# S6_Solenoid_Valve_Interlock.net
KiCad netlist of a schematic drawn in Altium Designer
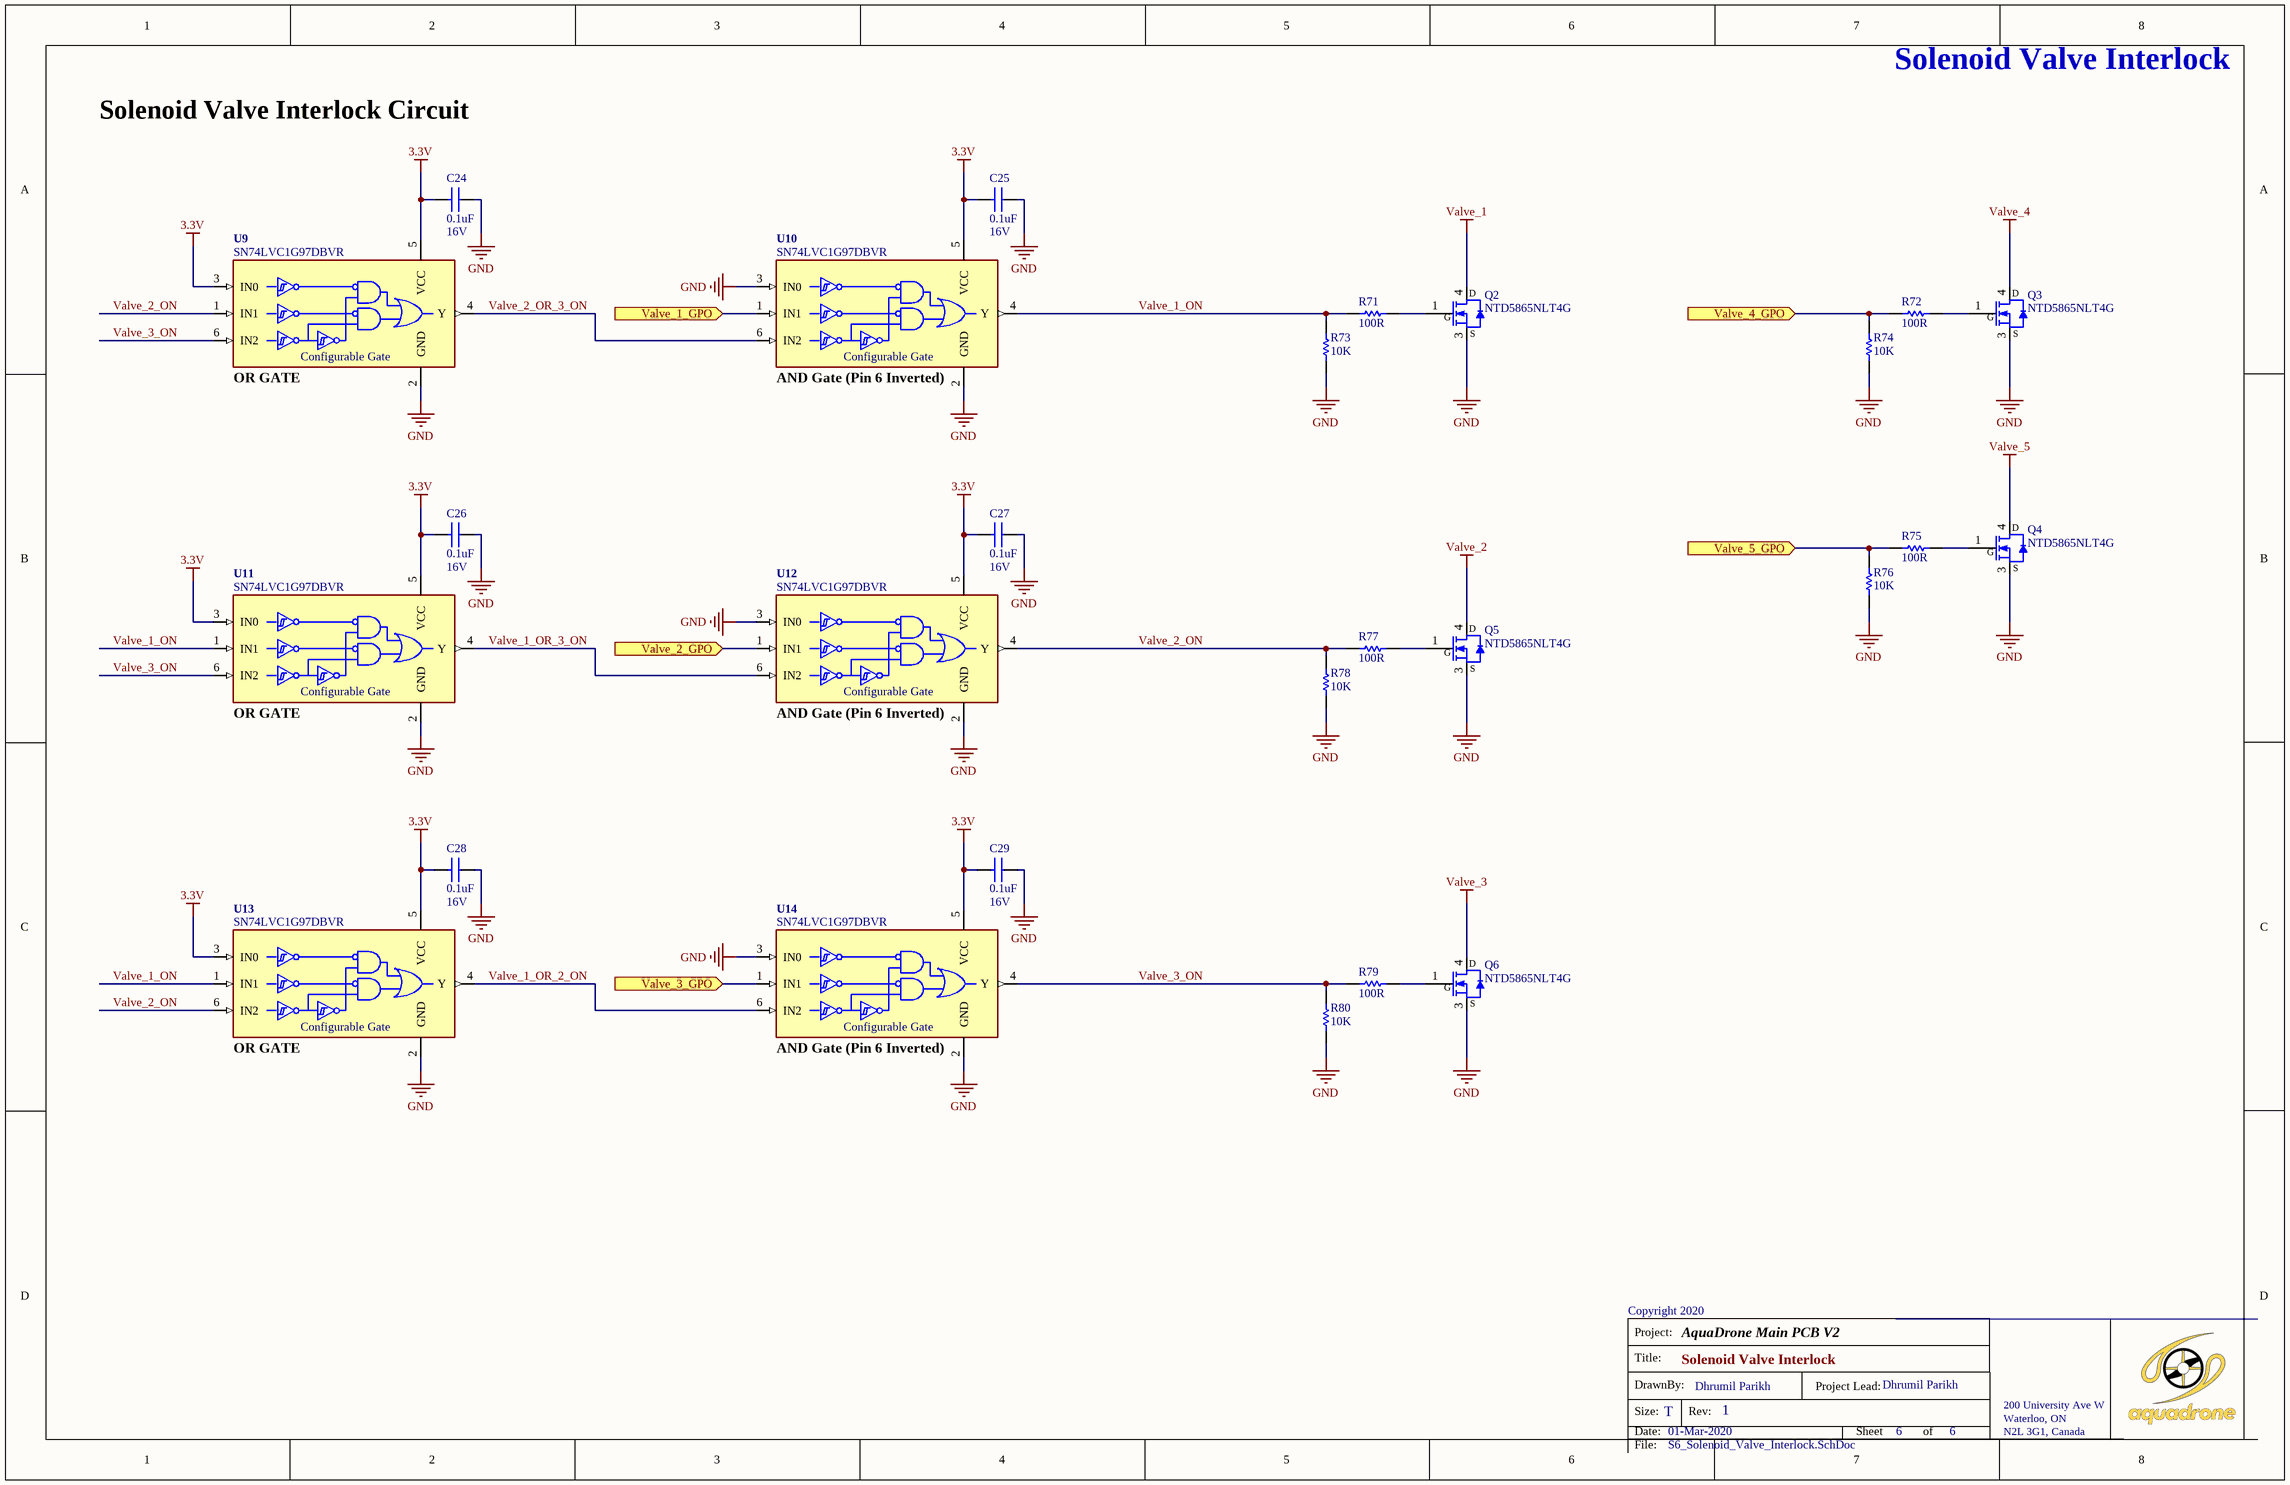
[diagram p0: S6_Solenoid_Valve_Interlock.SchDoc]

(export (version "E")
  (design (tool "Eeschema 10.0.6"))
  (components
    (comp (ref "C24")
      (value "0.1uF")
      (footprint "RWMN:CAPC1608X09N")
      (description "CAP CER 0.1UF 16V X7R 0603")
      (fields
        (field (name "MFG") "KEMET")
        (field (name "MFG_PART_NO") "C0603C104M4RACTU")
        (field (name "VOLTAGE") "16V")
      )
      (libsource (lib "AquaDrone") (part "CAP CER 0.1UF 16V X7R 0603"))
    )
    (comp (ref "C25")
      (value "0.1uF")
      (footprint "RWMN:CAPC1608X09N")
      (description "CAP CER 0.1UF 16V X7R 0603")
      (fields
        (field (name "MFG") "KEMET")
        (field (name "MFG_PART_NO") "C0603C104M4RACTU")
        (field (name "VOLTAGE") "16V")
      )
      (libsource (lib "AquaDrone") (part "CAP CER 0.1UF 16V X7R 0603"))
    )
    (comp (ref "C26")
      (value "0.1uF")
      (footprint "RWMN:CAPC1608X09N")
      (description "CAP CER 0.1UF 16V X7R 0603")
      (fields
        (field (name "MFG") "KEMET")
        (field (name "MFG_PART_NO") "C0603C104M4RACTU")
        (field (name "VOLTAGE") "16V")
      )
      (libsource (lib "AquaDrone") (part "CAP CER 0.1UF 16V X7R 0603"))
    )
    (comp (ref "C27")
      (value "0.1uF")
      (footprint "RWMN:CAPC1608X09N")
      (description "CAP CER 0.1UF 16V X7R 0603")
      (fields
        (field (name "MFG") "KEMET")
        (field (name "MFG_PART_NO") "C0603C104M4RACTU")
        (field (name "VOLTAGE") "16V")
      )
      (libsource (lib "AquaDrone") (part "CAP CER 0.1UF 16V X7R 0603"))
    )
    (comp (ref "C28")
      (value "0.1uF")
      (footprint "RWMN:CAPC1608X09N")
      (description "CAP CER 0.1UF 16V X7R 0603")
      (fields
        (field (name "MFG") "KEMET")
        (field (name "MFG_PART_NO") "C0603C104M4RACTU")
        (field (name "VOLTAGE") "16V")
      )
      (libsource (lib "AquaDrone") (part "CAP CER 0.1UF 16V X7R 0603"))
    )
    (comp (ref "C29")
      (value "0.1uF")
      (footprint "RWMN:CAPC1608X09N")
      (description "CAP CER 0.1UF 16V X7R 0603")
      (fields
        (field (name "MFG") "KEMET")
        (field (name "MFG_PART_NO") "C0603C104M4RACTU")
        (field (name "VOLTAGE") "16V")
      )
      (libsource (lib "AquaDrone") (part "CAP CER 0.1UF 16V X7R 0603"))
    )
    (comp (ref "Q2")
      (value "MOSFET N-CH 60V 46A DPAK")
      (footprint "TO229P990X238-4N")
      (fields (field (name "MFG") "ON Semiconductor") (field (name "MFG_PART_NO") "NTD5865NLT4G"))
      (libsource (lib "AquaDrone") (part "MOSFET N-CH 60V 46A DPAK"))
    )
    (comp (ref "Q3")
      (value "MOSFET N-CH 60V 46A DPAK")
      (footprint "TO229P990X238-4N")
      (fields (field (name "MFG") "ON Semiconductor") (field (name "MFG_PART_NO") "NTD5865NLT4G"))
      (libsource (lib "AquaDrone") (part "MOSFET N-CH 60V 46A DPAK"))
    )
    (comp (ref "Q4")
      (value "MOSFET N-CH 60V 46A DPAK")
      (footprint "TO229P990X238-4N")
      (fields (field (name "MFG") "ON Semiconductor") (field (name "MFG_PART_NO") "NTD5865NLT4G"))
      (libsource (lib "AquaDrone") (part "MOSFET N-CH 60V 46A DPAK"))
    )
    (comp (ref "Q5")
      (value "MOSFET N-CH 60V 46A DPAK")
      (footprint "TO229P990X238-4N")
      (fields (field (name "MFG") "ON Semiconductor") (field (name "MFG_PART_NO") "NTD5865NLT4G"))
      (libsource (lib "AquaDrone") (part "MOSFET N-CH 60V 46A DPAK"))
    )
    (comp (ref "Q6")
      (value "MOSFET N-CH 60V 46A DPAK")
      (footprint "TO229P990X238-4N")
      (fields (field (name "MFG") "ON Semiconductor") (field (name "MFG_PART_NO") "NTD5865NLT4G"))
      (libsource (lib "AquaDrone") (part "MOSFET N-CH 60V 46A DPAK"))
    )
    (comp (ref "R71")
      (value "100R")
      (footprint "RESC1608X06N")
      (description "RES SMD 100 OHM 1% 1/10W 0603")
      (fields (field (name "MFG") "Yageo") (field (name "MFG_PART_NO") "RC0603FR-07100RL"))
      (libsource (lib "AquaDrone") (part "RES SMD 100 OHM 1% 1/10W 0603"))
    )
    (comp (ref "R72")
      (value "100R")
      (footprint "RESC1608X06N")
      (description "RES SMD 100 OHM 1% 1/10W 0603")
      (fields (field (name "MFG") "Yageo") (field (name "MFG_PART_NO") "RC0603FR-07100RL"))
      (libsource (lib "AquaDrone") (part "RES SMD 100 OHM 1% 1/10W 0603"))
    )
    (comp (ref "R73")
      (value "10K")
      (footprint "RESC1608X06N")
      (description "RES SMD 10K OHM 1% 1/10W 0603")
      (fields (field (name "MFG") "Vishay Dale") (field (name "MFG_PART_NO") "CRCW060310K0FKEA"))
      (libsource (lib "AquaDrone") (part "RES SMD 10K OHM 1% 1/10W 0603"))
    )
    (comp (ref "R74")
      (value "10K")
      (footprint "RESC1608X06N")
      (description "RES SMD 10K OHM 1% 1/10W 0603")
      (fields (field (name "MFG") "Vishay Dale") (field (name "MFG_PART_NO") "CRCW060310K0FKEA"))
      (libsource (lib "AquaDrone") (part "RES SMD 10K OHM 1% 1/10W 0603"))
    )
    (comp (ref "R75")
      (value "100R")
      (footprint "RESC1608X06N")
      (description "RES SMD 100 OHM 1% 1/10W 0603")
      (fields (field (name "MFG") "Yageo") (field (name "MFG_PART_NO") "RC0603FR-07100RL"))
      (libsource (lib "AquaDrone") (part "RES SMD 100 OHM 1% 1/10W 0603"))
    )
    (comp (ref "R76")
      (value "10K")
      (footprint "RESC1608X06N")
      (description "RES SMD 10K OHM 1% 1/10W 0603")
      (fields (field (name "MFG") "Vishay Dale") (field (name "MFG_PART_NO") "CRCW060310K0FKEA"))
      (libsource (lib "AquaDrone") (part "RES SMD 10K OHM 1% 1/10W 0603"))
    )
    (comp (ref "R77")
      (value "100R")
      (footprint "RESC1608X06N")
      (description "RES SMD 100 OHM 1% 1/10W 0603")
      (fields (field (name "MFG") "Yageo") (field (name "MFG_PART_NO") "RC0603FR-07100RL"))
      (libsource (lib "AquaDrone") (part "RES SMD 100 OHM 1% 1/10W 0603"))
    )
    (comp (ref "R78")
      (value "10K")
      (footprint "RESC1608X06N")
      (description "RES SMD 10K OHM 1% 1/10W 0603")
      (fields (field (name "MFG") "Vishay Dale") (field (name "MFG_PART_NO") "CRCW060310K0FKEA"))
      (libsource (lib "AquaDrone") (part "RES SMD 10K OHM 1% 1/10W 0603"))
    )
    (comp (ref "R79")
      (value "100R")
      (footprint "RESC1608X06N")
      (description "RES SMD 100 OHM 1% 1/10W 0603")
      (fields (field (name "MFG") "Yageo") (field (name "MFG_PART_NO") "RC0603FR-07100RL"))
      (libsource (lib "AquaDrone") (part "RES SMD 100 OHM 1% 1/10W 0603"))
    )
    (comp (ref "R80")
      (value "10K")
      (footprint "RESC1608X06N")
      (description "RES SMD 10K OHM 1% 1/10W 0603")
      (fields (field (name "MFG") "Vishay Dale") (field (name "MFG_PART_NO") "CRCW060310K0FKEA"))
      (libsource (lib "AquaDrone") (part "RES SMD 10K OHM 1% 1/10W 0603"))
    )
    (comp (ref "U9")
      (value "SN74LVC1G97DBVR")
      (footprint "SOT65P210X110-6N_SN74LVC1G97DCK")
      (description "IC CONFIG MULT-FUNC GATE SOT23-6")
      (fields (field (name "MFG") "TI"))
      (libsource (lib "AquaDrone") (part "IC CONFIG MULT-FUNC GATE SOT23-6"))
    )
    (comp (ref "U10")
      (value "SN74LVC1G97DBVR")
      (footprint "SOT65P210X110-6N_SN74LVC1G97DCK")
      (description "IC CONFIG MULT-FUNC GATE SOT23-6")
      (fields (field (name "MFG") "TI"))
      (libsource (lib "AquaDrone") (part "IC CONFIG MULT-FUNC GATE SOT23-6"))
    )
    (comp (ref "U11")
      (value "SN74LVC1G97DBVR")
      (footprint "SOT65P210X110-6N_SN74LVC1G97DCK")
      (description "IC CONFIG MULT-FUNC GATE SOT23-6")
      (fields (field (name "MFG") "TI"))
      (libsource (lib "AquaDrone") (part "IC CONFIG MULT-FUNC GATE SOT23-6"))
    )
    (comp (ref "U12")
      (value "SN74LVC1G97DBVR")
      (footprint "SOT65P210X110-6N_SN74LVC1G97DCK")
      (description "IC CONFIG MULT-FUNC GATE SOT23-6")
      (fields (field (name "MFG") "TI"))
      (libsource (lib "AquaDrone") (part "IC CONFIG MULT-FUNC GATE SOT23-6"))
    )
    (comp (ref "U13")
      (value "SN74LVC1G97DBVR")
      (footprint "SOT65P210X110-6N_SN74LVC1G97DCK")
      (description "IC CONFIG MULT-FUNC GATE SOT23-6")
      (fields (field (name "MFG") "TI"))
      (libsource (lib "AquaDrone") (part "IC CONFIG MULT-FUNC GATE SOT23-6"))
    )
    (comp (ref "U14")
      (value "SN74LVC1G97DBVR")
      (footprint "SOT65P210X110-6N_SN74LVC1G97DCK")
      (description "IC CONFIG MULT-FUNC GATE SOT23-6")
      (fields (field (name "MFG") "TI"))
      (libsource (lib "AquaDrone") (part "IC CONFIG MULT-FUNC GATE SOT23-6"))
    )
  )
  (nets
    (net (code "1") (name "/Valve_1_GPO") (class "Default")
      (node (ref "U10") (pin "1") (pinfunction "IN1_1") (pintype "input"))
    )
    (net (code "2") (name "/Valve_1_ON") (class "Default")
      (node (ref "R71") (pin "1") (pinfunction "1_1") (pintype "passive"))
      (node (ref "R73") (pin "2") (pinfunction "2_2") (pintype "passive"))
      (node (ref "U10") (pin "4") (pinfunction "Y_4") (pintype "output"))
      (node (ref "U11") (pin "1") (pinfunction "IN1_1") (pintype "input"))
      (node (ref "U13") (pin "1") (pinfunction "IN1_1") (pintype "input"))
    )
    (net (code "3") (name "/Valve_1_OR_2_ON") (class "Default")
      (node (ref "U13") (pin "4") (pinfunction "Y_4") (pintype "output"))
      (node (ref "U14") (pin "6") (pinfunction "IN2_6") (pintype "input"))
    )
    (net (code "4") (name "/Valve_1_OR_3_ON") (class "Default")
      (node (ref "U11") (pin "4") (pinfunction "Y_4") (pintype "output"))
      (node (ref "U12") (pin "6") (pinfunction "IN2_6") (pintype "input"))
    )
    (net (code "5") (name "/Valve_2_GPO") (class "Default")
      (node (ref "U12") (pin "1") (pinfunction "IN1_1") (pintype "input"))
    )
    (net (code "6") (name "/Valve_2_ON") (class "Default")
      (node (ref "R77") (pin "1") (pinfunction "1_1") (pintype "passive"))
      (node (ref "R78") (pin "2") (pinfunction "2_2") (pintype "passive"))
      (node (ref "U12") (pin "4") (pinfunction "Y_4") (pintype "output"))
      (node (ref "U13") (pin "6") (pinfunction "IN2_6") (pintype "input"))
      (node (ref "U9") (pin "1") (pinfunction "IN1_1") (pintype "input"))
    )
    (net (code "7") (name "/Valve_2_OR_3_ON") (class "Default")
      (node (ref "U10") (pin "6") (pinfunction "IN2_6") (pintype "input"))
      (node (ref "U9") (pin "4") (pinfunction "Y_4") (pintype "output"))
    )
    (net (code "8") (name "/Valve_3_GPO") (class "Default")
      (node (ref "U14") (pin "1") (pinfunction "IN1_1") (pintype "input"))
    )
    (net (code "9") (name "/Valve_3_ON") (class "Default")
      (node (ref "R79") (pin "1") (pinfunction "1_1") (pintype "passive"))
      (node (ref "R80") (pin "2") (pinfunction "2_2") (pintype "passive"))
      (node (ref "U11") (pin "6") (pinfunction "IN2_6") (pintype "input"))
      (node (ref "U14") (pin "4") (pinfunction "Y_4") (pintype "output"))
      (node (ref "U9") (pin "6") (pinfunction "IN2_6") (pintype "input"))
    )
    (net (code "10") (name "/Valve_4_GPO") (class "Default")
      (node (ref "R72") (pin "1") (pinfunction "1_1") (pintype "passive"))
      (node (ref "R74") (pin "2") (pinfunction "2_2") (pintype "passive"))
    )
    (net (code "11") (name "/Valve_5_GPO") (class "Default")
      (node (ref "R75") (pin "1") (pinfunction "1_1") (pintype "passive"))
      (node (ref "R76") (pin "2") (pinfunction "2_2") (pintype "passive"))
    )
    (net (code "12") (name "3.3V") (class "Default")
      (node (ref "C24") (pin "2") (pinfunction "2_2") (pintype "passive"))
      (node (ref "C25") (pin "2") (pinfunction "2_2") (pintype "passive"))
      (node (ref "C26") (pin "2") (pinfunction "2_2") (pintype "passive"))
      (node (ref "C27") (pin "2") (pinfunction "2_2") (pintype "passive"))
      (node (ref "C28") (pin "2") (pinfunction "2_2") (pintype "passive"))
      (node (ref "C29") (pin "2") (pinfunction "2_2") (pintype "passive"))
      (node (ref "U10") (pin "5") (pinfunction "VCC_5") (pintype "power_in"))
      (node (ref "U11") (pin "3") (pinfunction "IN0_3") (pintype "input"))
      (node (ref "U11") (pin "5") (pinfunction "VCC_5") (pintype "power_in"))
      (node (ref "U12") (pin "5") (pinfunction "VCC_5") (pintype "power_in"))
      (node (ref "U13") (pin "3") (pinfunction "IN0_3") (pintype "input"))
      (node (ref "U13") (pin "5") (pinfunction "VCC_5") (pintype "power_in"))
      (node (ref "U14") (pin "5") (pinfunction "VCC_5") (pintype "power_in"))
      (node (ref "U9") (pin "3") (pinfunction "IN0_3") (pintype "input"))
      (node (ref "U9") (pin "5") (pinfunction "VCC_5") (pintype "power_in"))
    )
    (net (code "13") (name "GND") (class "Default")
      (node (ref "C24") (pin "1") (pinfunction "1_1") (pintype "passive"))
      (node (ref "C25") (pin "1") (pinfunction "1_1") (pintype "passive"))
      (node (ref "C26") (pin "1") (pinfunction "1_1") (pintype "passive"))
      (node (ref "C27") (pin "1") (pinfunction "1_1") (pintype "passive"))
      (node (ref "C28") (pin "1") (pinfunction "1_1") (pintype "passive"))
      (node (ref "C29") (pin "1") (pinfunction "1_1") (pintype "passive"))
      (node (ref "Q2") (pin "3") (pinfunction "S_3") (pintype "power_in"))
      (node (ref "Q3") (pin "3") (pinfunction "S_3") (pintype "power_in"))
      (node (ref "Q4") (pin "3") (pinfunction "S_3") (pintype "power_in"))
      (node (ref "Q5") (pin "3") (pinfunction "S_3") (pintype "power_in"))
      (node (ref "Q6") (pin "3") (pinfunction "S_3") (pintype "power_in"))
      (node (ref "R73") (pin "1") (pinfunction "1_1") (pintype "passive"))
      (node (ref "R74") (pin "1") (pinfunction "1_1") (pintype "passive"))
      (node (ref "R76") (pin "1") (pinfunction "1_1") (pintype "passive"))
      (node (ref "R78") (pin "1") (pinfunction "1_1") (pintype "passive"))
      (node (ref "R80") (pin "1") (pinfunction "1_1") (pintype "passive"))
      (node (ref "U10") (pin "2") (pinfunction "GND_2") (pintype "power_in"))
      (node (ref "U10") (pin "3") (pinfunction "IN0_3") (pintype "input"))
      (node (ref "U11") (pin "2") (pinfunction "GND_2") (pintype "power_in"))
      (node (ref "U12") (pin "2") (pinfunction "GND_2") (pintype "power_in"))
      (node (ref "U12") (pin "3") (pinfunction "IN0_3") (pintype "input"))
      (node (ref "U13") (pin "2") (pinfunction "GND_2") (pintype "power_in"))
      (node (ref "U14") (pin "2") (pinfunction "GND_2") (pintype "power_in"))
      (node (ref "U14") (pin "3") (pinfunction "IN0_3") (pintype "input"))
      (node (ref "U9") (pin "2") (pinfunction "GND_2") (pintype "power_in"))
    )
    (net (code "14") (name "Net-(Q2-G)") (class "Default")
      (node (ref "Q2") (pin "1") (pinfunction "G_1") (pintype "tri_state"))
      (node (ref "R71") (pin "2") (pinfunction "2_2") (pintype "passive"))
    )
    (net (code "15") (name "Net-(Q3-G)") (class "Default")
      (node (ref "Q3") (pin "1") (pinfunction "G_1") (pintype "tri_state"))
      (node (ref "R72") (pin "2") (pinfunction "2_2") (pintype "passive"))
    )
    (net (code "16") (name "Net-(Q4-G)") (class "Default")
      (node (ref "Q4") (pin "1") (pinfunction "G_1") (pintype "tri_state"))
      (node (ref "R75") (pin "2") (pinfunction "2_2") (pintype "passive"))
    )
    (net (code "17") (name "Net-(Q5-G)") (class "Default")
      (node (ref "Q5") (pin "1") (pinfunction "G_1") (pintype "tri_state"))
      (node (ref "R77") (pin "2") (pinfunction "2_2") (pintype "passive"))
    )
    (net (code "18") (name "Net-(Q6-G)") (class "Default")
      (node (ref "Q6") (pin "1") (pinfunction "G_1") (pintype "tri_state"))
      (node (ref "R79") (pin "2") (pinfunction "2_2") (pintype "passive"))
    )
    (net (code "19") (name "Valve_1") (class "Default")
      (node (ref "Q2") (pin "4") (pinfunction "D_4") (pintype "power_in"))
    )
    (net (code "20") (name "Valve_2") (class "Default")
      (node (ref "Q5") (pin "4") (pinfunction "D_4") (pintype "power_in"))
    )
    (net (code "21") (name "Valve_3") (class "Default")
      (node (ref "Q6") (pin "4") (pinfunction "D_4") (pintype "power_in"))
    )
    (net (code "22") (name "Valve_4") (class "Default")
      (node (ref "Q3") (pin "4") (pinfunction "D_4") (pintype "power_in"))
    )
    (net (code "23") (name "Valve_5") (class "Default")
      (node (ref "Q4") (pin "4") (pinfunction "D_4") (pintype "power_in"))
    )
  )
)
